# ece411-t4-rx-hand-controlled-robot.net
KiCad netlist of a schematic drawn in EAGLE
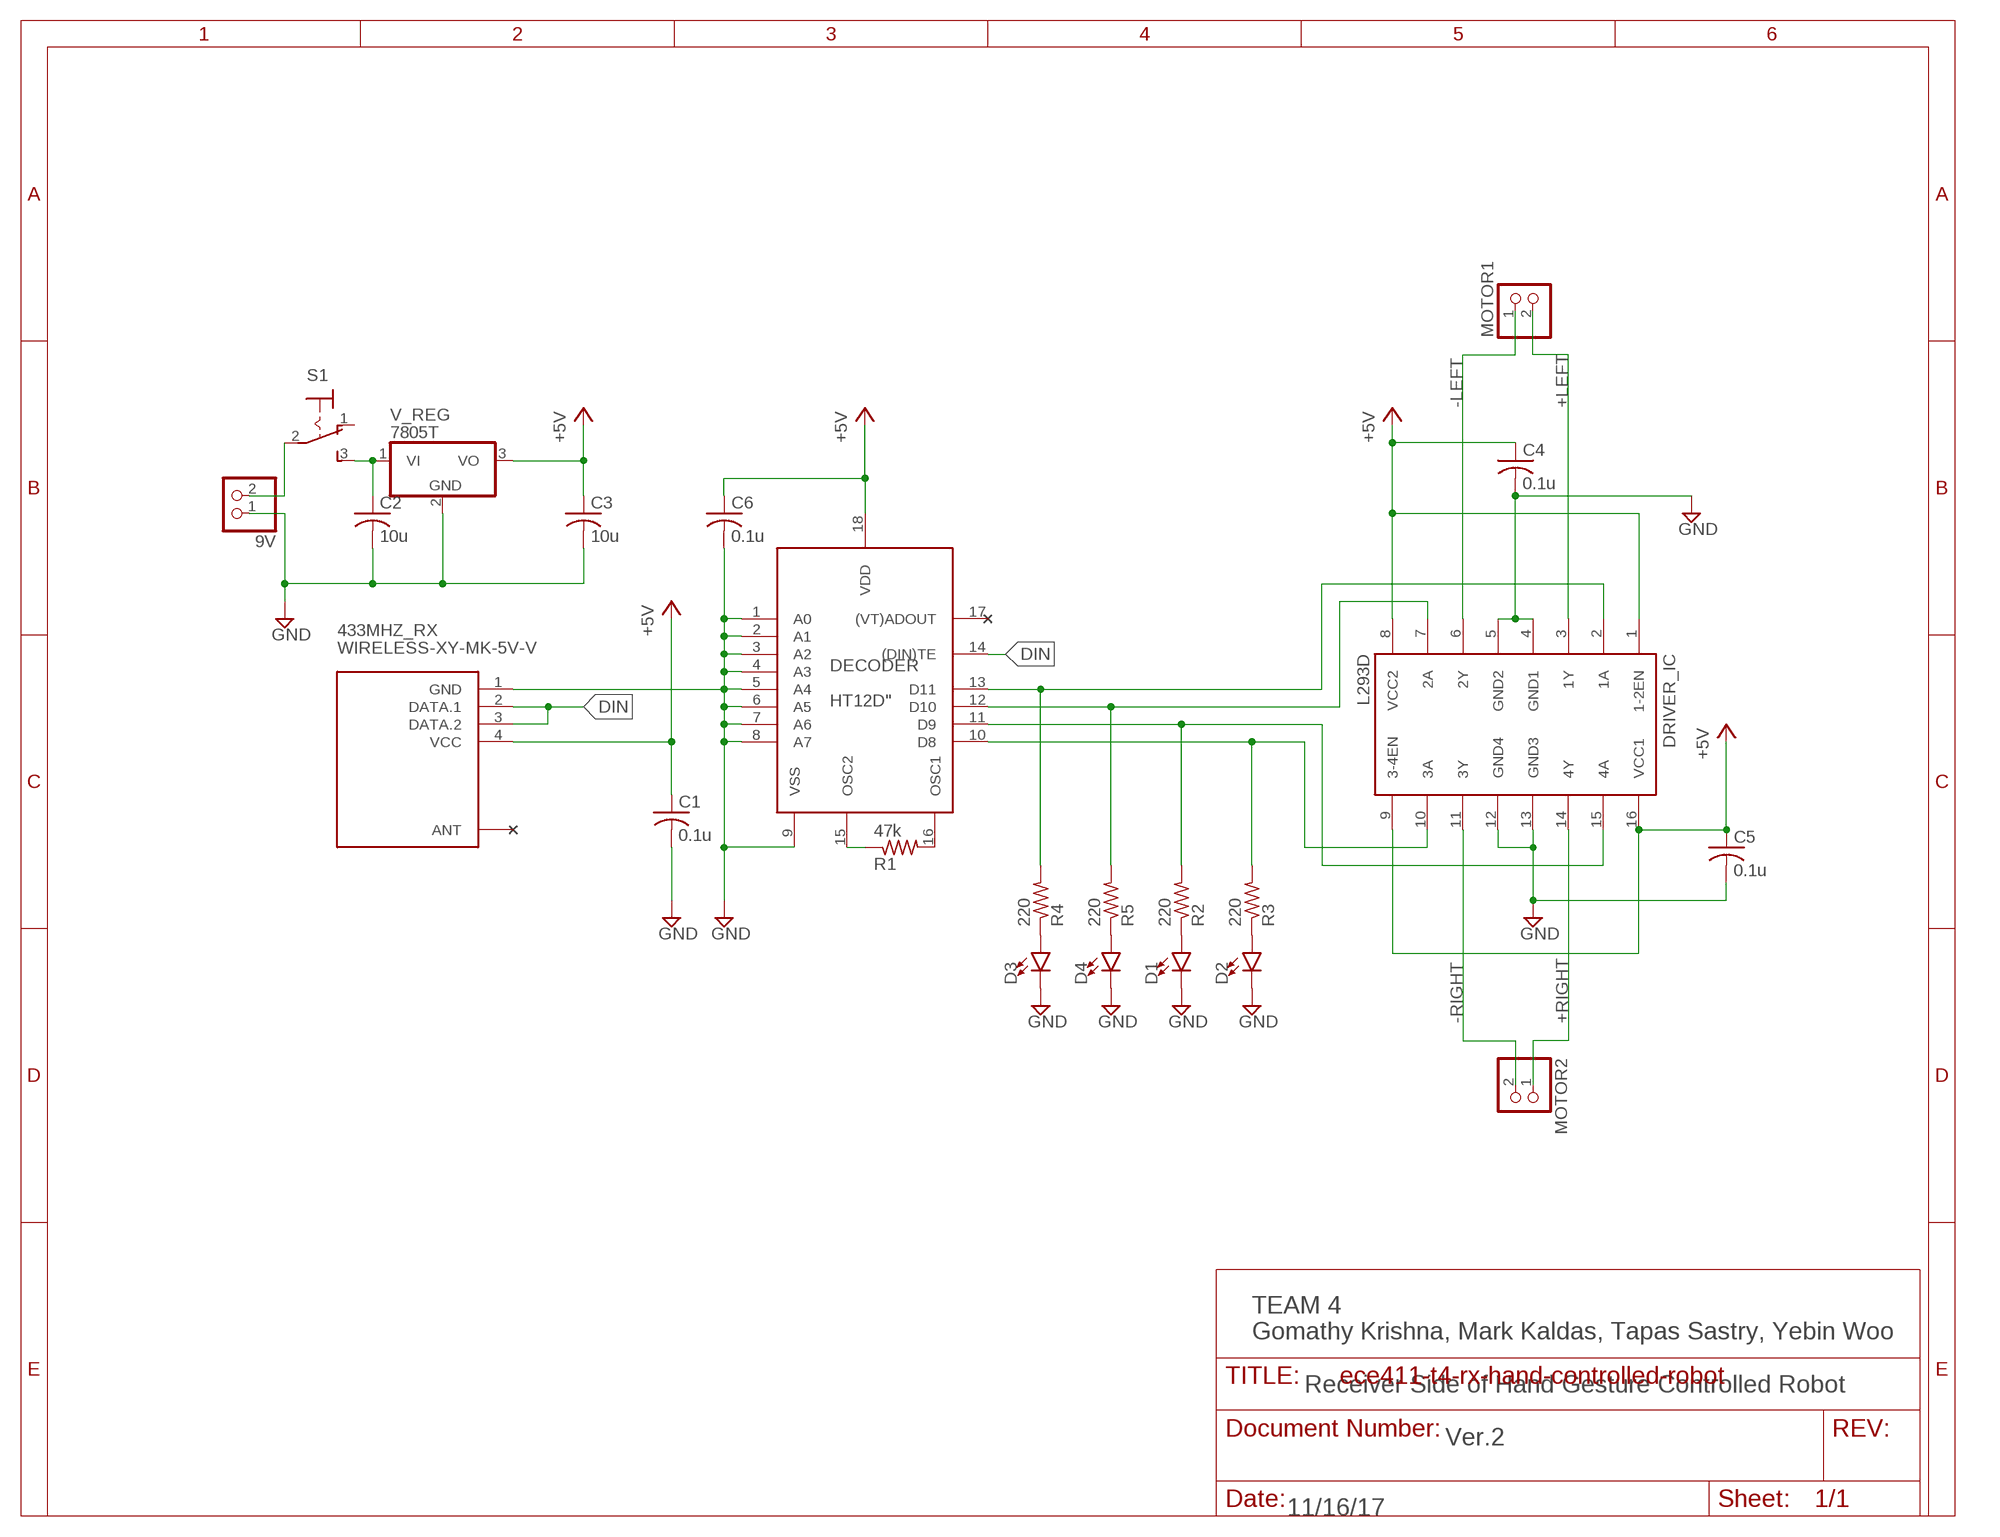
[diagram p0: schematic, sheet 1]

(export (version "E")
  (design (tool "Eeschema 10.0.6"))
  (components
    (comp (ref "9V")
      (value "PINHD-1X2")
      (footprint "eagle-import:1X02")
      (libsource (lib "eagle-import") (part "PINHD-1X2"))
    )
    (comp (ref "433MHZ_RX")
      (value "WIRELESS-XY-MK-5V-V")
      (footprint "eagle-import:WIRELESS-XY-MK-5V#V")
      (libsource (lib "eagle-import") (part "WIRELESS-XY-MK-5V-V"))
    )
    (comp (ref "C1")
      (value "0.1u")
      (footprint "eagle-import:C0805")
      (libsource (lib "eagle-import") (part "C-USC0805"))
    )
    (comp (ref "C2")
      (value "10u")
      (footprint "eagle-import:C0805")
      (libsource (lib "eagle-import") (part "C-USC0805"))
    )
    (comp (ref "C3")
      (value "10u")
      (footprint "eagle-import:C0805")
      (libsource (lib "eagle-import") (part "C-USC0805"))
    )
    (comp (ref "C4")
      (value "0.1u")
      (footprint "eagle-import:C0805")
      (libsource (lib "eagle-import") (part "C-USC0805"))
    )
    (comp (ref "C5")
      (value "0.1u")
      (footprint "eagle-import:C0805")
      (libsource (lib "eagle-import") (part "C-USC0805"))
    )
    (comp (ref "C6")
      (value "0.1u")
      (footprint "eagle-import:C0805")
      (libsource (lib "eagle-import") (part "C-USC0805"))
    )
    (comp (ref "D1")
      (value "LED3MM")
      (footprint "eagle-import:LED_3MM")
      (libsource (lib "eagle-import") (part "LED3MM"))
    )
    (comp (ref "D2")
      (value "LED3MM")
      (footprint "eagle-import:LED_3MM")
      (libsource (lib "eagle-import") (part "LED3MM"))
    )
    (comp (ref "D3")
      (value "LED3MM")
      (footprint "eagle-import:LED_3MM")
      (libsource (lib "eagle-import") (part "LED3MM"))
    )
    (comp (ref "D4")
      (value "LED3MM")
      (footprint "eagle-import:LED_3MM")
      (libsource (lib "eagle-import") (part "LED3MM"))
    )
    (comp (ref "DECODER")
      (value "HT12D\"")
      (footprint "eagle-import:18-DIP-A")
      (libsource (lib "eagle-import") (part "HT12D{dblquote}"))
    )
    (comp (ref "DRIVER_IC")
      (value "L293D")
      (footprint "eagle-import:DIL16")
      (libsource (lib "eagle-import") (part "L293D"))
    )
    (comp (ref "MOTOR1")
      (value "PINHD-1X2")
      (footprint "eagle-import:1X02")
      (libsource (lib "eagle-import") (part "PINHD-1X2"))
    )
    (comp (ref "MOTOR2")
      (value "PINHD-1X2")
      (footprint "eagle-import:1X02")
      (libsource (lib "eagle-import") (part "PINHD-1X2"))
    )
    (comp (ref "R1")
      (value "47k")
      (footprint "eagle-import:R0805")
      (libsource (lib "eagle-import") (part "R-US_R0805"))
    )
    (comp (ref "R2")
      (value "220")
      (footprint "eagle-import:R0805")
      (libsource (lib "eagle-import") (part "R-US_R0805"))
    )
    (comp (ref "R3")
      (value "220")
      (footprint "eagle-import:R0805")
      (libsource (lib "eagle-import") (part "R-US_R0805"))
    )
    (comp (ref "R4")
      (value "220")
      (footprint "eagle-import:R0805")
      (libsource (lib "eagle-import") (part "R-US_R0805"))
    )
    (comp (ref "R5")
      (value "220")
      (footprint "eagle-import:R0805")
      (libsource (lib "eagle-import") (part "R-US_R0805"))
    )
    (comp (ref "S1")
      (value "M9040P")
      (footprint "eagle-import:M9040P")
      (libsource (lib "eagle-import") (part "M9040P"))
    )
    (comp (ref "V_REG")
      (value "7805T")
      (footprint "eagle-import:TO220H")
      (libsource (lib "eagle-import") (part "78T05"))
    )
  )
  (nets
    (net (code "1") (name "+5V") (class "Default")
      (node (ref "433MHZ_RX") (pin "4") (pinfunction "VCC_4") (pintype "bidirectional"))
      (node (ref "C1") (pin "1") (pinfunction "1_1") (pintype "passive"))
      (node (ref "C3") (pin "1") (pinfunction "1_1") (pintype "passive"))
      (node (ref "C4") (pin "1") (pinfunction "1_1") (pintype "passive"))
      (node (ref "C5") (pin "1") (pinfunction "1_1") (pintype "passive"))
      (node (ref "C6") (pin "1") (pinfunction "1_1") (pintype "passive"))
      (node (ref "DECODER") (pin "18") (pinfunction "VDD_18") (pintype "power_in"))
      (node (ref "DRIVER_IC") (pin "1") (pinfunction "1-2EN_1") (pintype "input"))
      (node (ref "DRIVER_IC") (pin "16") (pinfunction "VCC1_16") (pintype "power_in"))
      (node (ref "DRIVER_IC") (pin "8") (pinfunction "VCC2_8") (pintype "power_in"))
      (node (ref "DRIVER_IC") (pin "9") (pinfunction "3-4EN_9") (pintype "input"))
      (node (ref "V_REG") (pin "3") (pinfunction "VO_3") (pintype "passive"))
    )
    (net (code "2") (name "/+LEFT") (class "Default")
      (node (ref "DRIVER_IC") (pin "3") (pinfunction "1Y_3") (pintype "output"))
      (node (ref "MOTOR1") (pin "2") (pinfunction "2_2") (pintype "passive"))
    )
    (net (code "3") (name "/+RIGHT") (class "Default")
      (node (ref "DRIVER_IC") (pin "14") (pinfunction "4Y_14") (pintype "output"))
      (node (ref "MOTOR2") (pin "1") (pinfunction "1_1") (pintype "passive"))
    )
    (net (code "4") (name "/-LEFT") (class "Default")
      (node (ref "DRIVER_IC") (pin "6") (pinfunction "2Y_6") (pintype "output"))
      (node (ref "MOTOR1") (pin "1") (pinfunction "1_1") (pintype "passive"))
    )
    (net (code "5") (name "/-RIGHT") (class "Default")
      (node (ref "DRIVER_IC") (pin "11") (pinfunction "3Y_11") (pintype "output"))
      (node (ref "MOTOR2") (pin "2") (pinfunction "2_2") (pintype "passive"))
    )
    (net (code "6") (name "DIN") (class "Default")
      (node (ref "433MHZ_RX") (pin "2") (pinfunction "DATA.1_2") (pintype "bidirectional"))
      (node (ref "433MHZ_RX") (pin "3") (pinfunction "DATA.2_3") (pintype "bidirectional"))
      (node (ref "DECODER") (pin "14") (pinfunction "(DIN)TE_14") (pintype "input"))
    )
    (net (code "7") (name "GND") (class "Default")
      (node (ref "433MHZ_RX") (pin "1") (pinfunction "GND_1") (pintype "bidirectional"))
      (node (ref "9V") (pin "1") (pinfunction "1_1") (pintype "passive"))
      (node (ref "C1") (pin "2") (pinfunction "2_2") (pintype "passive"))
      (node (ref "C2") (pin "2") (pinfunction "2_2") (pintype "passive"))
      (node (ref "C3") (pin "2") (pinfunction "2_2") (pintype "passive"))
      (node (ref "C4") (pin "2") (pinfunction "2_2") (pintype "passive"))
      (node (ref "C5") (pin "2") (pinfunction "2_2") (pintype "passive"))
      (node (ref "C6") (pin "2") (pinfunction "2_2") (pintype "passive"))
      (node (ref "D1") (pin "K") (pinfunction "C_K") (pintype "passive"))
      (node (ref "D2") (pin "K") (pinfunction "C_K") (pintype "passive"))
      (node (ref "D3") (pin "K") (pinfunction "C_K") (pintype "passive"))
      (node (ref "D4") (pin "K") (pinfunction "C_K") (pintype "passive"))
      (node (ref "DECODER") (pin "1") (pinfunction "A0_1") (pintype "input"))
      (node (ref "DECODER") (pin "2") (pinfunction "A1_2") (pintype "input"))
      (node (ref "DECODER") (pin "3") (pinfunction "A2_3") (pintype "input"))
      (node (ref "DECODER") (pin "4") (pinfunction "A3_4") (pintype "input"))
      (node (ref "DECODER") (pin "5") (pinfunction "A4_5") (pintype "input"))
      (node (ref "DECODER") (pin "6") (pinfunction "A5_6") (pintype "input"))
      (node (ref "DECODER") (pin "7") (pinfunction "A6_7") (pintype "input"))
      (node (ref "DECODER") (pin "8") (pinfunction "A7_8") (pintype "input"))
      (node (ref "DECODER") (pin "9") (pinfunction "VSS_9") (pintype "power_in"))
      (node (ref "DRIVER_IC") (pin "12") (pinfunction "GND4_12") (pintype "power_in"))
      (node (ref "DRIVER_IC") (pin "13") (pinfunction "GND3_13") (pintype "power_in"))
      (node (ref "DRIVER_IC") (pin "4") (pinfunction "GND1_4") (pintype "power_in"))
      (node (ref "DRIVER_IC") (pin "5") (pinfunction "GND2_5") (pintype "power_in"))
      (node (ref "V_REG") (pin "2") (pinfunction "GND_2") (pintype "passive"))
    )
    (net (code "8") (name "Net-(D1-PadA)") (class "Default")
      (node (ref "D1") (pin "A") (pinfunction "A_A") (pintype "passive"))
      (node (ref "R2") (pin "1") (pinfunction "1_1") (pintype "passive"))
    )
    (net (code "9") (name "Net-(D2-PadA)") (class "Default")
      (node (ref "D2") (pin "A") (pinfunction "A_A") (pintype "passive"))
      (node (ref "R3") (pin "1") (pinfunction "1_1") (pintype "passive"))
    )
    (net (code "10") (name "Net-(D3-PadA)") (class "Default")
      (node (ref "D3") (pin "A") (pinfunction "A_A") (pintype "passive"))
      (node (ref "R4") (pin "1") (pinfunction "1_1") (pintype "passive"))
    )
    (net (code "11") (name "Net-(D4-PadA)") (class "Default")
      (node (ref "D4") (pin "A") (pinfunction "A_A") (pintype "passive"))
      (node (ref "R5") (pin "1") (pinfunction "1_1") (pintype "passive"))
    )
    (net (code "12") (name "Net-(DECODER-D8)") (class "Default")
      (node (ref "DECODER") (pin "10") (pinfunction "D8_10") (pintype "output"))
      (node (ref "DRIVER_IC") (pin "10") (pinfunction "3A_10") (pintype "input"))
      (node (ref "R3") (pin "2") (pinfunction "2_2") (pintype "passive"))
    )
    (net (code "13") (name "Net-(DECODER-D9)") (class "Default")
      (node (ref "DECODER") (pin "11") (pinfunction "D9_11") (pintype "output"))
      (node (ref "DRIVER_IC") (pin "15") (pinfunction "4A_15") (pintype "input"))
      (node (ref "R2") (pin "2") (pinfunction "2_2") (pintype "passive"))
    )
    (net (code "14") (name "Net-(DECODER-D10)") (class "Default")
      (node (ref "DECODER") (pin "12") (pinfunction "D10_12") (pintype "output"))
      (node (ref "DRIVER_IC") (pin "7") (pinfunction "2A_7") (pintype "input"))
      (node (ref "R5") (pin "2") (pinfunction "2_2") (pintype "passive"))
    )
    (net (code "15") (name "Net-(DECODER-D11)") (class "Default")
      (node (ref "DECODER") (pin "13") (pinfunction "D11_13") (pintype "output"))
      (node (ref "DRIVER_IC") (pin "2") (pinfunction "1A_2") (pintype "input"))
      (node (ref "R4") (pin "2") (pinfunction "2_2") (pintype "passive"))
    )
    (net (code "16") (name "Net-(DECODER-OSC1)") (class "Default")
      (node (ref "DECODER") (pin "16") (pinfunction "OSC1_16") (pintype "input"))
      (node (ref "R1") (pin "2") (pinfunction "2_2") (pintype "passive"))
    )
    (net (code "17") (name "Net-(DECODER-OSC2)") (class "Default")
      (node (ref "DECODER") (pin "15") (pinfunction "OSC2_15") (pintype "output"))
      (node (ref "R1") (pin "1") (pinfunction "1_1") (pintype "passive"))
    )
    (net (code "18") (name "Net-(S1-P)") (class "Default")
      (node (ref "9V") (pin "2") (pinfunction "2_2") (pintype "passive"))
      (node (ref "S1") (pin "2") (pinfunction "P_2") (pintype "passive"))
    )
    (net (code "19") (name "Net-(S1-S)") (class "Default")
      (node (ref "C2") (pin "1") (pinfunction "1_1") (pintype "passive"))
      (node (ref "S1") (pin "3") (pinfunction "S_3") (pintype "passive"))
      (node (ref "V_REG") (pin "1") (pinfunction "VI_1") (pintype "input"))
    )
    (net (code "20") (name "unconnected-(433MHZ_RX-PadANT)") (class "Default")
      (node (ref "433MHZ_RX") (pin "ANT") (pinfunction "ANT_ANT") (pintype "output"))
    )
    (net (code "21") (name "unconnected-(DECODER-(VT)ADOUT-Pad17)") (class "Default")
      (node (ref "DECODER") (pin "17") (pinfunction "(VT)ADOUT_17") (pintype "output"))
    )
    (net (code "22") (name "unconnected-(S1-O-Pad1)") (class "Default")
      (node (ref "S1") (pin "1") (pinfunction "O_1") (pintype "passive"))
    )
  )
)
